# MIC2260x_Module.net
KiCad netlist of a schematic drawn in EAGLE
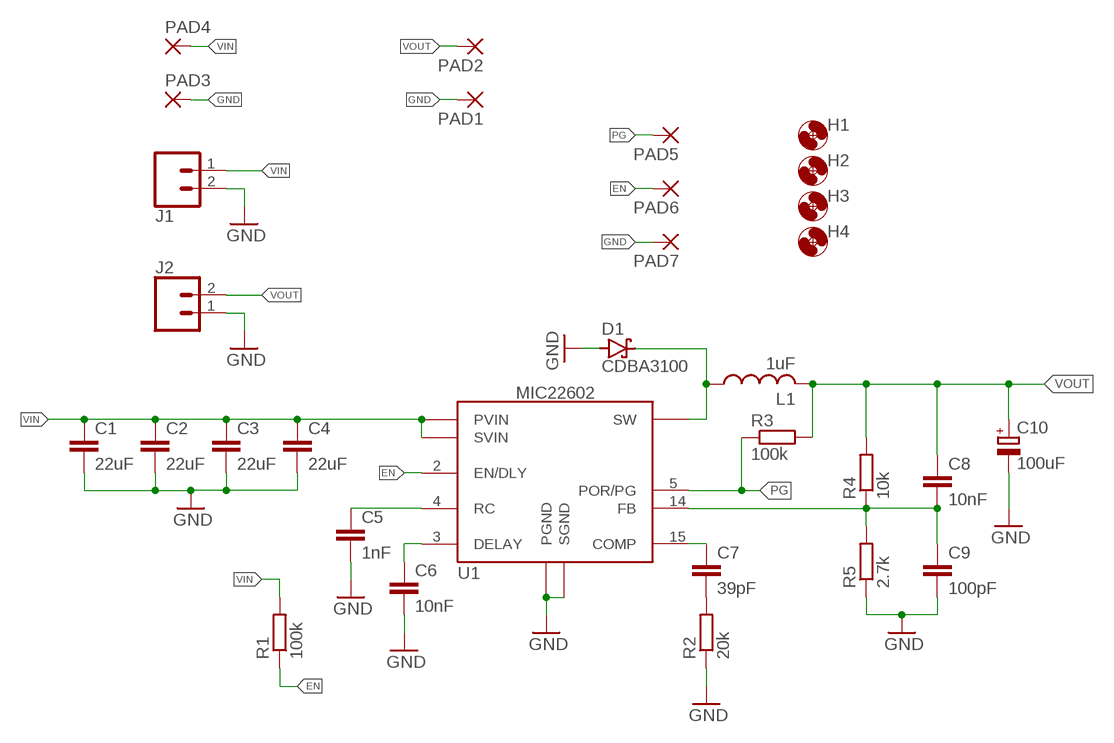
[diagram p0: schematic, sheet 1]

(export (version "E")
  (design (tool "Eeschema 10.0.6"))
  (components
    (comp (ref "C1")
      (value "22uF")
      (footprint "eagle-import:C0805")
      (fields (field (name "MF") "Murata") (field (name "MPN") "GRM219R61C226ME15L"))
      (libsource (lib "eagle-import") (part "C-EUC080522UF"))
    )
    (comp (ref "C2")
      (value "22uF")
      (footprint "eagle-import:C0805")
      (fields (field (name "MF") "Murata") (field (name "MPN") "GRM219R61C226ME15L"))
      (libsource (lib "eagle-import") (part "C-EUC080522UF"))
    )
    (comp (ref "C3")
      (value "22uF")
      (footprint "eagle-import:C0805")
      (fields (field (name "MF") "Murata") (field (name "MPN") "GRM219R61C226ME15L"))
      (libsource (lib "eagle-import") (part "C-EUC080522UF"))
    )
    (comp (ref "C4")
      (value "22uF")
      (footprint "eagle-import:C0805")
      (fields (field (name "MF") "Murata") (field (name "MPN") "GRM219R61C226ME15L"))
      (libsource (lib "eagle-import") (part "C-EUC080522UF"))
    )
    (comp (ref "C5")
      (value "1nF")
      (footprint "eagle-import:C0402")
      (libsource (lib "eagle-import") (part "C-EUC0402"))
    )
    (comp (ref "C6")
      (value "10nF")
      (footprint "eagle-import:C0402")
      (libsource (lib "eagle-import") (part "C-EUC0402"))
    )
    (comp (ref "C7")
      (value "39pF")
      (footprint "eagle-import:C0402")
      (libsource (lib "eagle-import") (part "C-EUC0402"))
    )
    (comp (ref "C8")
      (value "10nF")
      (footprint "eagle-import:C0402")
      (libsource (lib "eagle-import") (part "C-EUC0402"))
    )
    (comp (ref "C9")
      (value "100pF")
      (footprint "eagle-import:C0402")
      (libsource (lib "eagle-import") (part "C-EUC0402"))
    )
    (comp (ref "C10")
      (value "100uF")
      (footprint "eagle-import:C1411_TANT")
      (libsource (lib "eagle-import") (part "CTANT_EU1411"))
    )
    (comp (ref "D1")
      (value "CDBA3100")
      (footprint "eagle-import:DO214AC")
      (libsource (lib "eagle-import") (part "DIODE_SCHOTTKYDO-214AC"))
    )
    (comp (ref "H1")
      (value "MOUNTING_HOLE4_NP")
      (footprint "eagle-import:4_40")
      (fields (field (name "MPN") "DNP"))
      (libsource (lib "eagle-import") (part "MOUNTING_HOLE4_NP"))
    )
    (comp (ref "H2")
      (value "MOUNTING_HOLE4_NP")
      (footprint "eagle-import:4_40")
      (fields (field (name "MPN") "DNP"))
      (libsource (lib "eagle-import") (part "MOUNTING_HOLE4_NP"))
    )
    (comp (ref "H3")
      (value "MOUNTING_HOLE4_NP")
      (footprint "eagle-import:4_40")
      (fields (field (name "MPN") "DNP"))
      (libsource (lib "eagle-import") (part "MOUNTING_HOLE4_NP"))
    )
    (comp (ref "H4")
      (value "MOUNTING_HOLE4_NP")
      (footprint "eagle-import:4_40")
      (fields (field (name "MPN") "DNP"))
      (libsource (lib "eagle-import") (part "MOUNTING_HOLE4_NP"))
    )
    (comp (ref "J1")
      (value "CONN_023.5MM_ROUND_RESTRICT")
      (footprint "eagle-import:SCREWTERMINAL-3.5MM-2_ROUND_RESTRICT")
      (fields (field (name "MF") "On Shore") (field (name "MPN") "OSTTE020161"))
      (libsource (lib "eagle-import") (part "CONN_023.5MM_ROUND_RESTRICT"))
    )
    (comp (ref "J2")
      (value "CONN_023.5MM_ROUND_RESTRICT")
      (footprint "eagle-import:SCREWTERMINAL-3.5MM-2_ROUND_RESTRICT")
      (fields (field (name "MF") "On Shore") (field (name "MPN") "OSTTE020161"))
      (libsource (lib "eagle-import") (part "CONN_023.5MM_ROUND_RESTRICT"))
    )
    (comp (ref "L1")
      (value "1uF")
      (footprint "eagle-import:WE-MAIA(4.1X4.1)")
      (libsource (lib "eagle-import") (part "INDUCTOR_MAIA_4.1X4.1"))
    )
    (comp (ref "PAD1")
      (value "SMD5")
      (footprint "eagle-import:SMD2,54-5,08")
      (libsource (lib "eagle-import") (part "SMD5"))
    )
    (comp (ref "PAD2")
      (value "SMD5")
      (footprint "eagle-import:SMD2,54-5,08")
      (libsource (lib "eagle-import") (part "SMD5"))
    )
    (comp (ref "PAD3")
      (value "SMD5")
      (footprint "eagle-import:SMD2,54-5,08")
      (libsource (lib "eagle-import") (part "SMD5"))
    )
    (comp (ref "PAD4")
      (value "SMD5")
      (footprint "eagle-import:SMD2,54-5,08")
      (libsource (lib "eagle-import") (part "SMD5"))
    )
    (comp (ref "PAD5")
      (value "SMD2")
      (footprint "eagle-import:SMD1,27-2,54")
      (fields (field (name "MPN") "DNP"))
      (libsource (lib "eagle-import") (part "SMD2"))
    )
    (comp (ref "PAD6")
      (value "SMD2")
      (footprint "eagle-import:SMD1,27-2,54")
      (fields (field (name "MPN") "DNP"))
      (libsource (lib "eagle-import") (part "SMD2"))
    )
    (comp (ref "PAD7")
      (value "SMD2")
      (footprint "eagle-import:SMD1,27-2,54")
      (fields (field (name "MPN") "DNP"))
      (libsource (lib "eagle-import") (part "SMD2"))
    )
    (comp (ref "R1")
      (value "100k")
      (footprint "eagle-import:R0402")
      (fields (field (name "MF") "Yageo") (field (name "MPN") "RC0402FR-07100KL"))
      (libsource (lib "eagle-import") (part "R-EU_R0402100K"))
    )
    (comp (ref "R2")
      (value "20k")
      (footprint "eagle-import:R0402")
      (fields (field (name "MF") "Yageo"))
      (libsource (lib "eagle-import") (part "R-EU_R0402"))
    )
    (comp (ref "R3")
      (value "100k")
      (footprint "eagle-import:R0402")
      (fields (field (name "MF") "Yageo") (field (name "MPN") "RC0402FR-07100KL"))
      (libsource (lib "eagle-import") (part "R-EU_R0402100K"))
    )
    (comp (ref "R4")
      (value "10k")
      (footprint "eagle-import:R0402")
      (fields (field (name "MF") "Yageo") (field (name "MPN") "RC0402FR-0710KL"))
      (libsource (lib "eagle-import") (part "R-EU_R040210K"))
    )
    (comp (ref "R5")
      (value "2.7k")
      (footprint "eagle-import:R0402")
      (fields (field (name "MF") "Yageo"))
      (libsource (lib "eagle-import") (part "R-EU_R0402"))
    )
    (comp (ref "U1")
      (value "MIC22602")
      (footprint "eagle-import:QFN24_POWER")
      (fields
        (field (name "DISP") "MIC22602")
        (field (name "MF") "Microchip")
        (field (name "MPN") "MIC22602YML-TR")
      )
      (libsource (lib "eagle-import") (part "MIC22602"))
    )
  )
  (nets
    (net (code "1") (name "EN") (class "Default")
      (node (ref "PAD6") (pin "1") (pinfunction "P_1") (pintype "passive"))
      (node (ref "R1") (pin "1") (pinfunction "1_1") (pintype "passive"))
      (node (ref "U1") (pin "2") (pinfunction "EN/DLY_2") (pintype "bidirectional"))
    )
    (net (code "2") (name "GND") (class "Default")
      (node (ref "C1") (pin "2") (pinfunction "2_2") (pintype "passive"))
      (node (ref "C10") (pin "CATHODE") (pinfunction "-_CATHODE") (pintype "passive"))
      (node (ref "C2") (pin "2") (pinfunction "2_2") (pintype "passive"))
      (node (ref "C3") (pin "2") (pinfunction "2_2") (pintype "passive"))
      (node (ref "C4") (pin "2") (pinfunction "2_2") (pintype "passive"))
      (node (ref "C5") (pin "2") (pinfunction "2_2") (pintype "passive"))
      (node (ref "C6") (pin "2") (pinfunction "2_2") (pintype "passive"))
      (node (ref "C9") (pin "2") (pinfunction "2_2") (pintype "passive"))
      (node (ref "D1") (pin "A") (pinfunction "A_A") (pintype "passive"))
      (node (ref "J1") (pin "2") (pinfunction "2_2") (pintype "passive"))
      (node (ref "J2") (pin "1") (pinfunction "1_1") (pintype "passive"))
      (node (ref "PAD1") (pin "1") (pinfunction "P_1") (pintype "passive"))
      (node (ref "PAD3") (pin "1") (pinfunction "P_1") (pintype "passive"))
      (node (ref "PAD7") (pin "1") (pinfunction "P_1") (pintype "passive"))
      (node (ref "R2") (pin "1") (pinfunction "1_1") (pintype "passive"))
      (node (ref "R5") (pin "1") (pinfunction "1_1") (pintype "passive"))
      (node (ref "U1") (pin "12") (pinfunction "PGND_12") (pintype "bidirectional"))
      (node (ref "U1") (pin "16") (pinfunction "SGND_16") (pintype "bidirectional"))
      (node (ref "U1") (pin "19") (pinfunction "PGND_19") (pintype "bidirectional"))
      (node (ref "U1") (pin "24") (pinfunction "PGND_24") (pintype "bidirectional"))
      (node (ref "U1") (pin "7") (pinfunction "PGND_7") (pintype "bidirectional"))
      (node (ref "U1") (pin "EP") (pinfunction "PGND_EP") (pintype "bidirectional"))
      (node (ref "U1") (pin "EP@1") (pinfunction "PGND_EP@1") (pintype "bidirectional"))
      (node (ref "U1") (pin "EP@2") (pinfunction "PGND_EP@2") (pintype "bidirectional"))
      (node (ref "U1") (pin "EP@3") (pinfunction "PGND_EP@3") (pintype "bidirectional"))
      (node (ref "U1") (pin "EP@4") (pinfunction "PGND_EP@4") (pintype "bidirectional"))
      (node (ref "U1") (pin "EP@5") (pinfunction "PGND_EP@5") (pintype "bidirectional"))
      (node (ref "U1") (pin "EP@6") (pinfunction "PGND_EP@6") (pintype "bidirectional"))
      (node (ref "U1") (pin "EP@7") (pinfunction "PGND_EP@7") (pintype "bidirectional"))
      (node (ref "U1") (pin "EP@8") (pinfunction "PGND_EP@8") (pintype "bidirectional"))
      (node (ref "U1") (pin "EP@9") (pinfunction "PGND_EP@9") (pintype "bidirectional"))
    )
    (net (code "3") (name "Net-(C7-Pad2)") (class "Default")
      (node (ref "C7") (pin "2") (pinfunction "2_2") (pintype "passive"))
      (node (ref "R2") (pin "2") (pinfunction "2_2") (pintype "passive"))
    )
    (net (code "4") (name "Net-(L1-1)") (class "Default")
      (node (ref "D1") (pin "C") (pinfunction "C_C") (pintype "passive"))
      (node (ref "L1") (pin "P$1") (pinfunction "1_P$1") (pintype "passive"))
      (node (ref "U1") (pin "10") (pinfunction "SW_10") (pintype "bidirectional"))
      (node (ref "U1") (pin "11") (pinfunction "SW_11") (pintype "bidirectional"))
      (node (ref "U1") (pin "20") (pinfunction "SW_20") (pintype "bidirectional"))
      (node (ref "U1") (pin "21") (pinfunction "SW_21") (pintype "bidirectional"))
      (node (ref "U1") (pin "22") (pinfunction "SW_22") (pintype "bidirectional"))
      (node (ref "U1") (pin "23") (pinfunction "SW_23") (pintype "bidirectional"))
      (node (ref "U1") (pin "8") (pinfunction "SW_8") (pintype "bidirectional"))
      (node (ref "U1") (pin "9") (pinfunction "SW_9") (pintype "bidirectional"))
    )
    (net (code "5") (name "Net-(U1-COMP)") (class "Default")
      (node (ref "C7") (pin "1") (pinfunction "1_1") (pintype "passive"))
      (node (ref "U1") (pin "15") (pinfunction "COMP_15") (pintype "bidirectional"))
    )
    (net (code "6") (name "Net-(U1-DELAY)") (class "Default")
      (node (ref "C6") (pin "1") (pinfunction "1_1") (pintype "passive"))
      (node (ref "U1") (pin "3") (pinfunction "DELAY_3") (pintype "bidirectional"))
    )
    (net (code "7") (name "Net-(U1-FB)") (class "Default")
      (node (ref "C8") (pin "2") (pinfunction "2_2") (pintype "passive"))
      (node (ref "C9") (pin "1") (pinfunction "1_1") (pintype "passive"))
      (node (ref "R4") (pin "1") (pinfunction "1_1") (pintype "passive"))
      (node (ref "R5") (pin "2") (pinfunction "2_2") (pintype "passive"))
      (node (ref "U1") (pin "14") (pinfunction "FB_14") (pintype "bidirectional"))
    )
    (net (code "8") (name "Net-(U1-RC)") (class "Default")
      (node (ref "C5") (pin "1") (pinfunction "1_1") (pintype "passive"))
      (node (ref "U1") (pin "4") (pinfunction "RC_4") (pintype "bidirectional"))
    )
    (net (code "9") (name "PG") (class "Default")
      (node (ref "PAD5") (pin "1") (pinfunction "P_1") (pintype "passive"))
      (node (ref "R3") (pin "1") (pinfunction "1_1") (pintype "passive"))
      (node (ref "U1") (pin "5") (pinfunction "POR/PG_5") (pintype "bidirectional"))
    )
    (net (code "10") (name "VIN") (class "Default")
      (node (ref "C1") (pin "1") (pinfunction "1_1") (pintype "passive"))
      (node (ref "C2") (pin "1") (pinfunction "1_1") (pintype "passive"))
      (node (ref "C3") (pin "1") (pinfunction "1_1") (pintype "passive"))
      (node (ref "C4") (pin "1") (pinfunction "1_1") (pintype "passive"))
      (node (ref "J1") (pin "1") (pinfunction "1_1") (pintype "passive"))
      (node (ref "PAD4") (pin "1") (pinfunction "P_1") (pintype "passive"))
      (node (ref "R1") (pin "2") (pinfunction "2_2") (pintype "passive"))
      (node (ref "U1") (pin "1") (pinfunction "PVIN_1") (pintype "bidirectional"))
      (node (ref "U1") (pin "13") (pinfunction "PVIN_13") (pintype "bidirectional"))
      (node (ref "U1") (pin "17") (pinfunction "SVIN_17") (pintype "bidirectional"))
      (node (ref "U1") (pin "18") (pinfunction "PVIN_18") (pintype "bidirectional"))
      (node (ref "U1") (pin "6") (pinfunction "PVIN_6") (pintype "bidirectional"))
    )
    (net (code "11") (name "VOUT") (class "Default")
      (node (ref "C10") (pin "ANODE") (pinfunction "+_ANODE") (pintype "passive"))
      (node (ref "C8") (pin "1") (pinfunction "1_1") (pintype "passive"))
      (node (ref "J2") (pin "2") (pinfunction "2_2") (pintype "passive"))
      (node (ref "L1") (pin "P$2") (pinfunction "2_P$2") (pintype "passive"))
      (node (ref "PAD2") (pin "1") (pinfunction "P_1") (pintype "passive"))
      (node (ref "R3") (pin "2") (pinfunction "2_2") (pintype "passive"))
      (node (ref "R4") (pin "2") (pinfunction "2_2") (pintype "passive"))
    )
  )
)
